# rev6.net
KiCad netlist of a schematic drawn in Altium Designer
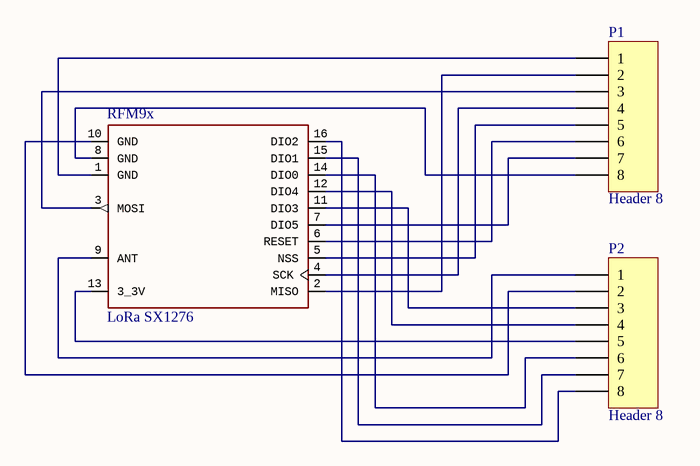
[diagram p0: rev6.SchDoc]

(export (version "E")
  (design (tool "Eeschema 10.0.6"))
  (components
    (comp (ref "P1")
      (value "Header 8")
      (footprint "HDR1X8")
      (description "Header, 8-Pin")
      (fields (field (name "PUBLISHER") "Altium Limited"))
      (libsource (lib "Miscellaneous Connectors") (part "Header 8"))
    )
    (comp (ref "P2")
      (value "Header 8")
      (footprint "HDR1X8")
      (description "Header, 8-Pin")
      (fields (field (name "PUBLISHER") "Altium Limited"))
      (libsource (lib "Miscellaneous Connectors") (part "Header 8"))
    )
    (comp (ref "RFM9x")
      (value "LoRa SX1276")
      (footprint "XCVR_RFM95W-868S2")
      (fields (field (name "MF") "RF") (field (name "MP") "RFM95W-868S2"))
      (libsource (lib "RFM95rev1") (part "RFM95W-868S2"))
    )
  )
  (nets
    (net (code "1") (name "Net-(P1-Pad1)") (class "Default")
      (node (ref "P1") (pin "1") (pinfunction "1_1") (pintype "passive"))
      (node (ref "RFM9x") (pin "1") (pinfunction "GND_1") (pintype "power_in"))
    )
    (net (code "2") (name "Net-(P1-Pad8)") (class "Default")
      (node (ref "P1") (pin "8") (pinfunction "8_8") (pintype "passive"))
      (node (ref "RFM9x") (pin "8") (pinfunction "GND_8") (pintype "power_in"))
    )
    (net (code "3") (name "Net-(P2-Pad2)") (class "Default")
      (node (ref "P2") (pin "2") (pinfunction "2_2") (pintype "passive"))
      (node (ref "RFM9x") (pin "10") (pinfunction "GND_10") (pintype "power_in"))
    )
    (net (code "4") (name "Net-(RFM9x-3_3V)") (class "Default")
      (node (ref "P2") (pin "5") (pinfunction "5_5") (pintype "passive"))
      (node (ref "RFM9x") (pin "13") (pinfunction "3_3V_13") (pintype "power_in"))
    )
    (net (code "5") (name "Net-(RFM9x-ANT)") (class "Default")
      (node (ref "P2") (pin "1") (pinfunction "1_1") (pintype "passive"))
      (node (ref "RFM9x") (pin "9") (pinfunction "ANT_9") (pintype "passive"))
    )
    (net (code "6") (name "Net-(RFM9x-DIO0)") (class "Default")
      (node (ref "P2") (pin "6") (pinfunction "6_6") (pintype "passive"))
      (node (ref "RFM9x") (pin "14") (pinfunction "DIO0_14") (pintype "passive"))
    )
    (net (code "7") (name "Net-(RFM9x-DIO1)") (class "Default")
      (node (ref "P2") (pin "7") (pinfunction "7_7") (pintype "passive"))
      (node (ref "RFM9x") (pin "15") (pinfunction "DIO1_15") (pintype "passive"))
    )
    (net (code "8") (name "Net-(RFM9x-DIO2)") (class "Default")
      (node (ref "P2") (pin "8") (pinfunction "8_8") (pintype "passive"))
      (node (ref "RFM9x") (pin "16") (pinfunction "DIO2_16") (pintype "passive"))
    )
    (net (code "9") (name "Net-(RFM9x-DIO3)") (class "Default")
      (node (ref "P2") (pin "3") (pinfunction "3_3") (pintype "passive"))
      (node (ref "RFM9x") (pin "11") (pinfunction "DIO3_11") (pintype "passive"))
    )
    (net (code "10") (name "Net-(RFM9x-DIO4)") (class "Default")
      (node (ref "P2") (pin "4") (pinfunction "4_4") (pintype "passive"))
      (node (ref "RFM9x") (pin "12") (pinfunction "DIO4_12") (pintype "passive"))
    )
    (net (code "11") (name "Net-(RFM9x-DIO5)") (class "Default")
      (node (ref "P1") (pin "7") (pinfunction "7_7") (pintype "passive"))
      (node (ref "RFM9x") (pin "7") (pinfunction "DIO5_7") (pintype "passive"))
    )
    (net (code "12") (name "Net-(RFM9x-MISO)") (class "Default")
      (node (ref "P1") (pin "2") (pinfunction "2_2") (pintype "passive"))
      (node (ref "RFM9x") (pin "2") (pinfunction "MISO_2") (pintype "passive"))
    )
    (net (code "13") (name "Net-(RFM9x-MOSI)") (class "Default")
      (node (ref "P1") (pin "3") (pinfunction "3_3") (pintype "passive"))
      (node (ref "RFM9x") (pin "3") (pinfunction "MOSI_3") (pintype "output"))
    )
    (net (code "14") (name "Net-(RFM9x-NSS)") (class "Default")
      (node (ref "P1") (pin "5") (pinfunction "5_5") (pintype "passive"))
      (node (ref "RFM9x") (pin "5") (pinfunction "NSS_5") (pintype "passive"))
    )
    (net (code "15") (name "Net-(RFM9x-RESET)") (class "Default")
      (node (ref "P1") (pin "6") (pinfunction "6_6") (pintype "passive"))
      (node (ref "RFM9x") (pin "6") (pinfunction "RESET_6") (pintype "passive"))
    )
    (net (code "16") (name "Net-(RFM9x-SCK)") (class "Default")
      (node (ref "P1") (pin "4") (pinfunction "4_4") (pintype "passive"))
      (node (ref "RFM9x") (pin "4") (pinfunction "SCK_4") (pintype "passive"))
    )
  )
)
